# GPSBee.net
KiCad netlist of a schematic drawn in EAGLE
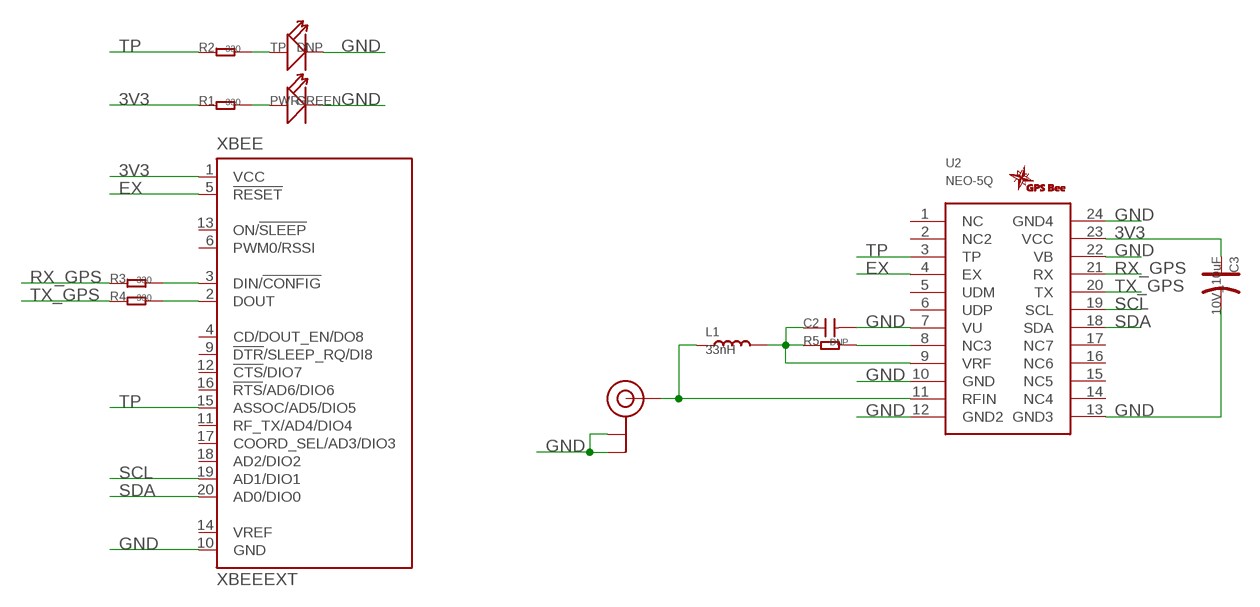
[diagram p0: schematic, sheet 1]

(export (version "E")
  (design (tool "Eeschema 10.0.6"))
  (components
    (comp (ref "C2")
      (value "C-0603")
      (footprint "eagle-import:0603")
      (libsource (lib "eagle-import") (part "C-0603"))
    )
    (comp (ref "C3")
      (value "10V_10uF")
      (footprint "eagle-import:AVX-A")
      (libsource (lib "eagle-import") (part "CAP-AVX-A"))
    )
    (comp (ref "L1")
      (value "33nH")
      (footprint "eagle-import:0603")
      (libsource (lib "eagle-import") (part "L0603"))
    )
    (comp (ref "LOGO1")
      (value "GPSLOGO_SLIK")
      (footprint "eagle-import:GPSLOGO")
      (libsource (lib "eagle-import") (part "GPSLOGO_SLIK"))
    )
    (comp (ref "PWR")
      (value "GREEN")
      (footprint "eagle-import:LED-0603")
      (libsource (lib "eagle-import") (part "LED'0603'"))
    )
    (comp (ref "R1")
      (value "330")
      (footprint "eagle-import:0603")
      (libsource (lib "eagle-import") (part "R-0603"))
    )
    (comp (ref "R2")
      (value "330")
      (footprint "eagle-import:0603")
      (libsource (lib "eagle-import") (part "R-0603"))
    )
    (comp (ref "R3")
      (value "330")
      (footprint "eagle-import:0603")
      (libsource (lib "eagle-import") (part "R-0603"))
    )
    (comp (ref "R4")
      (value "330")
      (footprint "eagle-import:0603")
      (libsource (lib "eagle-import") (part "R-0603"))
    )
    (comp (ref "R5")
      (value "DNP")
      (footprint "eagle-import:0603")
      (libsource (lib "eagle-import") (part "R-0603"))
    )
    (comp (ref "TP")
      (value "DNP")
      (footprint "eagle-import:LED-0603")
      (libsource (lib "eagle-import") (part "LED'0603'"))
    )
    (comp (ref "U2")
      (value "NEO-5Q")
      (footprint "eagle-import:NEO-5Q")
      (libsource (lib "eagle-import") (part "NEO-5Q"))
    )
    (comp (ref "U3")
      (value "U.FL")
      (footprint "eagle-import:U.FL")
      (libsource (lib "eagle-import") (part "U.FL"))
    )
    (comp (ref "XBEE")
      (value "XBEEEXT")
      (footprint "eagle-import:XBEE_PLUG")
      (libsource (lib "eagle-import") (part "XBEEEXT"))
    )
  )
  (nets
    (net (code "1") (name "/3V3") (class "Default")
      (node (ref "C3") (pin "+") (pinfunction "+_+") (pintype "passive"))
      (node (ref "R1") (pin "1") (pinfunction "1_1") (pintype "passive"))
      (node (ref "U2") (pin "23") (pinfunction "VCC_23") (pintype "bidirectional"))
      (node (ref "XBEE") (pin "1") (pinfunction "VCC_1") (pintype "power_in"))
    )
    (net (code "2") (name "/EX") (class "Default")
      (node (ref "U2") (pin "4") (pinfunction "EX_4") (pintype "bidirectional"))
      (node (ref "XBEE") (pin "5") (pinfunction "~{RESET}_5") (pintype "input"))
    )
    (net (code "3") (name "/GND") (class "Default")
      (node (ref "C2") (pin "2") (pinfunction "2_2") (pintype "passive"))
      (node (ref "C3") (pin "-") (pinfunction "-_-") (pintype "passive"))
      (node (ref "PWR") (pin "-") (pinfunction "-_-") (pintype "passive"))
      (node (ref "TP") (pin "-") (pinfunction "-_-") (pintype "passive"))
      (node (ref "U2") (pin "10") (pinfunction "GND_10") (pintype "bidirectional"))
      (node (ref "U2") (pin "12") (pinfunction "GND2_12") (pintype "bidirectional"))
      (node (ref "U2") (pin "13") (pinfunction "GND3_13") (pintype "bidirectional"))
      (node (ref "U2") (pin "22") (pinfunction "VB_22") (pintype "bidirectional"))
      (node (ref "U2") (pin "24") (pinfunction "GND4_24") (pintype "bidirectional"))
      (node (ref "U2") (pin "7") (pinfunction "VU_7") (pintype "bidirectional"))
      (node (ref "U3") (pin "P$1") (pinfunction "GND_P$1") (pintype "bidirectional"))
      (node (ref "U3") (pin "P$2") (pinfunction "GND_P$2") (pintype "bidirectional"))
      (node (ref "XBEE") (pin "10") (pinfunction "GND_10") (pintype "bidirectional"))
    )
    (net (code "4") (name "/RX_GPS") (class "Default")
      (node (ref "R3") (pin "1") (pinfunction "1_1") (pintype "passive"))
      (node (ref "U2") (pin "21") (pinfunction "RX_21") (pintype "bidirectional"))
    )
    (net (code "5") (name "/SCL") (class "Default")
      (node (ref "U2") (pin "19") (pinfunction "SCL_19") (pintype "bidirectional"))
      (node (ref "XBEE") (pin "19") (pinfunction "AD1/DIO1_19") (pintype "bidirectional"))
    )
    (net (code "6") (name "/SDA") (class "Default")
      (node (ref "U2") (pin "18") (pinfunction "SDA_18") (pintype "bidirectional"))
      (node (ref "XBEE") (pin "20") (pinfunction "AD0/DIO0_20") (pintype "bidirectional"))
    )
    (net (code "7") (name "/TP") (class "Default")
      (node (ref "R2") (pin "1") (pinfunction "1_1") (pintype "passive"))
      (node (ref "U2") (pin "3") (pinfunction "TP_3") (pintype "bidirectional"))
      (node (ref "XBEE") (pin "15") (pinfunction "ASSOC/AD5/DIO5_15") (pintype "bidirectional"))
    )
    (net (code "8") (name "/TX_GPS") (class "Default")
      (node (ref "R4") (pin "1") (pinfunction "1_1") (pintype "passive"))
      (node (ref "U2") (pin "20") (pinfunction "TX_20") (pintype "bidirectional"))
    )
    (net (code "9") (name "Net-(PWR-Pad+)") (class "Default")
      (node (ref "PWR") (pin "+") (pinfunction "+_+") (pintype "passive"))
      (node (ref "R1") (pin "2") (pinfunction "2_2") (pintype "passive"))
    )
    (net (code "10") (name "Net-(R2-Pad2)") (class "Default")
      (node (ref "R2") (pin "2") (pinfunction "2_2") (pintype "passive"))
      (node (ref "TP") (pin "+") (pinfunction "+_+") (pintype "passive"))
    )
    (net (code "11") (name "Net-(U2-NC3)") (class "Default")
      (node (ref "R5") (pin "2") (pinfunction "2_2") (pintype "passive"))
      (node (ref "U2") (pin "8") (pinfunction "NC3_8") (pintype "bidirectional"))
    )
    (net (code "12") (name "Net-(U2-RFIN)") (class "Default")
      (node (ref "L1") (pin "1") (pinfunction "1_1") (pintype "passive"))
      (node (ref "U2") (pin "11") (pinfunction "RFIN_11") (pintype "bidirectional"))
      (node (ref "U3") (pin "P$3") (pinfunction "SIGNAL_P$3") (pintype "bidirectional"))
    )
    (net (code "13") (name "Net-(U2-VRF)") (class "Default")
      (node (ref "C2") (pin "1") (pinfunction "1_1") (pintype "passive"))
      (node (ref "L1") (pin "2") (pinfunction "2_2") (pintype "passive"))
      (node (ref "R5") (pin "1") (pinfunction "1_1") (pintype "passive"))
      (node (ref "U2") (pin "9") (pinfunction "VRF_9") (pintype "bidirectional"))
    )
    (net (code "14") (name "Net-(XBEE-DIN{slash}~{CONFIG})") (class "Default")
      (node (ref "R3") (pin "2") (pinfunction "2_2") (pintype "passive"))
      (node (ref "XBEE") (pin "3") (pinfunction "DIN/~{CONFIG}_3") (pintype "input"))
    )
    (net (code "15") (name "Net-(XBEE-DOUT)") (class "Default")
      (node (ref "R4") (pin "2") (pinfunction "2_2") (pintype "passive"))
      (node (ref "XBEE") (pin "2") (pinfunction "DOUT_2") (pintype "output"))
    )
    (net (code "16") (name "unconnected-(U2-NC-Pad1)") (class "Default")
      (node (ref "U2") (pin "1") (pinfunction "NC_1") (pintype "bidirectional"))
    )
    (net (code "17") (name "unconnected-(U2-NC2-Pad2)") (class "Default")
      (node (ref "U2") (pin "2") (pinfunction "NC2_2") (pintype "bidirectional"))
    )
    (net (code "18") (name "unconnected-(U2-NC4-Pad14)") (class "Default")
      (node (ref "U2") (pin "14") (pinfunction "NC4_14") (pintype "bidirectional"))
    )
    (net (code "19") (name "unconnected-(U2-NC5-Pad15)") (class "Default")
      (node (ref "U2") (pin "15") (pinfunction "NC5_15") (pintype "bidirectional"))
    )
    (net (code "20") (name "unconnected-(U2-NC6-Pad16)") (class "Default")
      (node (ref "U2") (pin "16") (pinfunction "NC6_16") (pintype "bidirectional"))
    )
    (net (code "21") (name "unconnected-(U2-NC7-Pad17)") (class "Default")
      (node (ref "U2") (pin "17") (pinfunction "NC7_17") (pintype "bidirectional"))
    )
    (net (code "22") (name "unconnected-(U2-UDM-Pad5)") (class "Default")
      (node (ref "U2") (pin "5") (pinfunction "UDM_5") (pintype "bidirectional"))
    )
    (net (code "23") (name "unconnected-(U2-UDP-Pad6)") (class "Default")
      (node (ref "U2") (pin "6") (pinfunction "UDP_6") (pintype "bidirectional"))
    )
    (net (code "24") (name "unconnected-(XBEE-AD2{slash}DIO2-Pad18)") (class "Default")
      (node (ref "XBEE") (pin "18") (pinfunction "AD2/DIO2_18") (pintype "bidirectional"))
    )
    (net (code "25") (name "unconnected-(XBEE-CD{slash}DOUT_EN{slash}DO8-Pad4)") (class "Default")
      (node (ref "XBEE") (pin "4") (pinfunction "CD/DOUT_EN/DO8_4") (pintype "output"))
    )
    (net (code "26") (name "unconnected-(XBEE-COORD_SEL{slash}AD3{slash}DIO3-Pad17)") (class "Default")
      (node (ref "XBEE") (pin "17") (pinfunction "COORD_SEL/AD3/DIO3_17") (pintype "bidirectional"))
    )
    (net (code "27") (name "unconnected-(XBEE-ON{slash}~{SLEEP}-Pad13)") (class "Default")
      (node (ref "XBEE") (pin "13") (pinfunction "ON/~{SLEEP}_13") (pintype "output"))
    )
    (net (code "28") (name "unconnected-(XBEE-PWM0{slash}RSSI-Pad6)") (class "Default")
      (node (ref "XBEE") (pin "6") (pinfunction "PWM0/RSSI_6") (pintype "output"))
    )
    (net (code "29") (name "unconnected-(XBEE-RF_TX{slash}AD4{slash}DIO4-Pad11)") (class "Default")
      (node (ref "XBEE") (pin "11") (pinfunction "RF_TX/AD4/DIO4_11") (pintype "bidirectional"))
    )
    (net (code "30") (name "unconnected-(XBEE-VREF-Pad14)") (class "Default")
      (node (ref "XBEE") (pin "14") (pinfunction "VREF_14") (pintype "input"))
    )
    (net (code "31") (name "unconnected-(XBEE-~{CTS}{slash}DIO7-Pad12)") (class "Default")
      (node (ref "XBEE") (pin "12") (pinfunction "~{CTS}/DIO7_12") (pintype "bidirectional"))
    )
    (net (code "32") (name "unconnected-(XBEE-~{DTR}{slash}SLEEP_RQ{slash}DI8-Pad9)") (class "Default")
      (node (ref "XBEE") (pin "9") (pinfunction "~{DTR}/SLEEP_RQ/DI8_9") (pintype "bidirectional"))
    )
    (net (code "33") (name "unconnected-(XBEE-~{RTS}{slash}AD6{slash}DIO6-Pad16)") (class "Default")
      (node (ref "XBEE") (pin "16") (pinfunction "~{RTS}/AD6/DIO6_16") (pintype "bidirectional"))
    )
  )
)
